# Applicaties.net
KiCad netlist of a schematic drawn in Altium Designer
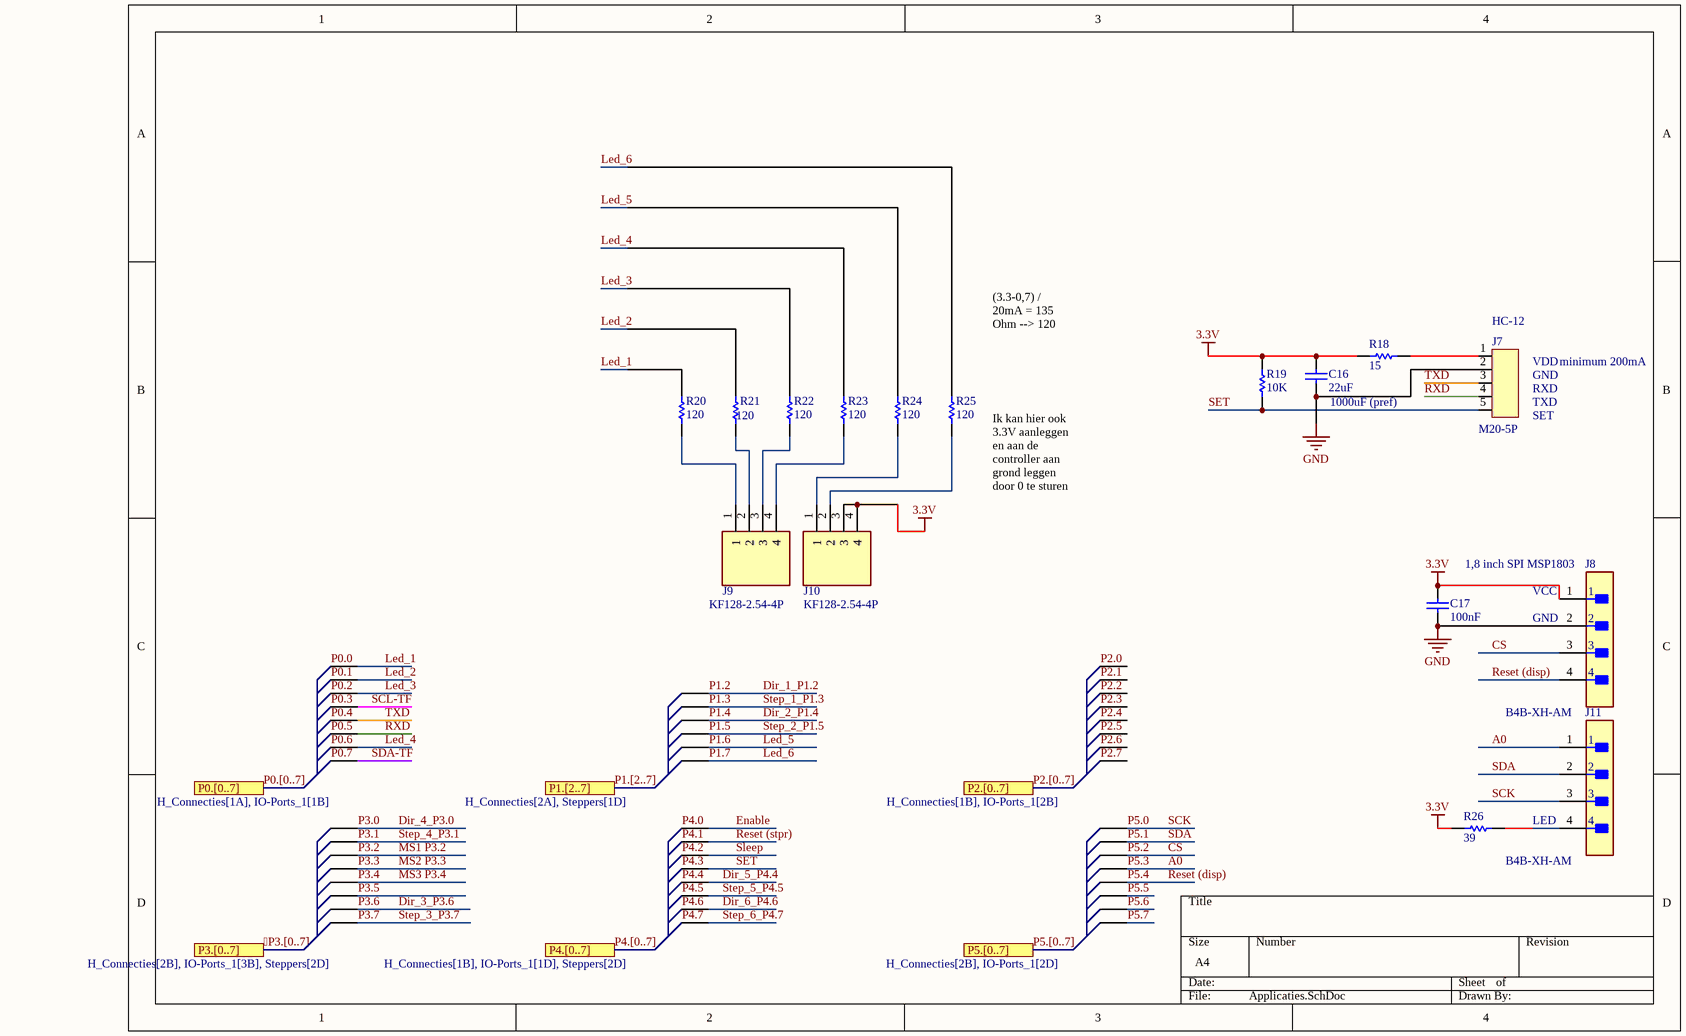
[diagram p0: Applicaties.SchDoc]

(export (version "E")
  (design (tool "Eeschema 10.0.6"))
  (components
    (comp (ref "C16")
      (value "22uF")
      (footprint "CAPC1608X90X35LL15T15")
      (fields
        (field (name "MANUFACTURER") "AVX Interconnect / Elco")
        (field (name "PART NUMBER") "0603ZC101KAT2A")
      )
      (libsource (lib "Altium Content Vault") (part "CAP"))
    )
    (comp (ref "C17")
      (value "100nF")
      (footprint "CAPC1608X90X35LL15T15")
      (fields
        (field (name "MANUFACTURER") "AVX Interconnect / Elco")
        (field (name "PART NUMBER") "0603ZC101KAT2A")
      )
      (libsource (lib "Altium Content Vault") (part "CAP"))
    )
    (comp (ref "J7")
      (value "M20-5P")
      (footprint "M20-5PIN")
      (libsource (lib "Eigen_schemas") (part "M20-5P"))
    )
    (comp (ref "J8")
      (value "B4B-XH-AM")
      (footprint "FP-B4B-XH-A_LF_SN-MFG")
      (description "CONN HEADER VERT 4POS 2.5MM")
      (libsource (lib "Altium Content Vault") (part "299a8cea1bdcbc3624fe62c390fa72c"))
    )
    (comp (ref "J9")
      (value "KF128-2.54-4P")
      (footprint "KF128-2.54-4P")
      (description "Connector")
      (libsource (lib "*") (part "KF128-2.54-4P"))
    )
    (comp (ref "J10")
      (value "KF128-2.54-4P")
      (footprint "KF128-2.54-4P")
      (description "Connector")
      (libsource (lib "*") (part "KF128-2.54-4P"))
    )
    (comp (ref "J11")
      (value "B4B-XH-AM")
      (footprint "FP-B4B-XH-A_LF_SN-MFG")
      (description "CONN HEADER VERT 4POS 2.5MM")
      (libsource (lib "Altium Content Vault") (part "299a8cea1bdcbc3624fe62c390fa72c"))
    )
    (comp (ref "R18")
      (value "15")
      (footprint "RESC1608X55X25LL10T15")
      (fields (field (name "PART NUMBER") "RC0603FR-102KL") (field (name "MANUFACTURER") "Yageo"))
      (libsource (lib "Altium Content Vault") (part "RES"))
    )
    (comp (ref "R19")
      (value "10K")
      (footprint "RESC1608X55X25LL10T15")
      (fields (field (name "PART NUMBER") "RC0603FR-102KL") (field (name "MANUFACTURER") "Yageo"))
      (libsource (lib "Altium Content Vault") (part "RES"))
    )
    (comp (ref "R20")
      (value "120")
      (footprint "RESC1608X55X25LL10T15")
      (fields (field (name "PART NUMBER") "RC0603FR-102KL") (field (name "MANUFACTURER") "Yageo"))
      (libsource (lib "Altium Content Vault") (part "RES"))
    )
    (comp (ref "R21")
      (value "120")
      (footprint "RESC1608X55X25LL10T15")
      (fields (field (name "PART NUMBER") "RC0603FR-102KL") (field (name "MANUFACTURER") "Yageo"))
      (libsource (lib "Altium Content Vault") (part "RES"))
    )
    (comp (ref "R22")
      (value "120")
      (footprint "RESC1608X55X25LL10T15")
      (fields (field (name "PART NUMBER") "RC0603FR-102KL") (field (name "MANUFACTURER") "Yageo"))
      (libsource (lib "Altium Content Vault") (part "RES"))
    )
    (comp (ref "R23")
      (value "120")
      (footprint "RESC1608X55X25LL10T15")
      (fields (field (name "PART NUMBER") "RC0603FR-102KL") (field (name "MANUFACTURER") "Yageo"))
      (libsource (lib "Altium Content Vault") (part "RES"))
    )
    (comp (ref "R24")
      (value "120")
      (footprint "RESC1608X55X25LL10T15")
      (fields (field (name "PART NUMBER") "RC0603FR-102KL") (field (name "MANUFACTURER") "Yageo"))
      (libsource (lib "Altium Content Vault") (part "RES"))
    )
    (comp (ref "R25")
      (value "120")
      (footprint "RESC1608X55X25LL10T15")
      (fields (field (name "PART NUMBER") "RC0603FR-102KL") (field (name "MANUFACTURER") "Yageo"))
      (libsource (lib "Altium Content Vault") (part "RES"))
    )
    (comp (ref "R26")
      (value "39")
      (footprint "RESC1608X55X25LL10T15")
      (fields (field (name "PART NUMBER") "RC0603FR-102KL") (field (name "MANUFACTURER") "Yageo"))
      (libsource (lib "Altium Content Vault") (part "RES"))
    )
  )
  (nets
    (net (code "18") (name "/P0.0") (class "Default")
      (node (ref "R20") (pin "1") (pinfunction "1_1") (pintype "passive"))
    )
    (net (code "19") (name "/P0.1") (class "Default")
      (node (ref "R21") (pin "1") (pinfunction "1_1") (pintype "passive"))
    )
    (net (code "20") (name "/P0.2") (class "Default")
      (node (ref "R22") (pin "1") (pinfunction "1_1") (pintype "passive"))
    )
    (net (code "22") (name "/P0.4") (class "Default")
      (node (ref "J7") (pin "3") (pinfunction "3_3") (pintype "passive"))
    )
    (net (code "23") (name "/P0.5") (class "Default")
      (node (ref "J7") (pin "4") (pinfunction "4_4") (pintype "passive"))
    )
    (net (code "24") (name "/P0.6") (class "Default")
      (node (ref "R23") (pin "1") (pinfunction "1_1") (pintype "passive"))
    )
    (net (code "31") (name "/P1.6") (class "Default")
      (node (ref "R24") (pin "1") (pinfunction "1_1") (pintype "passive"))
    )
    (net (code "32") (name "/P1.7") (class "Default")
      (node (ref "R25") (pin "1") (pinfunction "1_1") (pintype "passive"))
    )
    (net (code "46") (name "/P4.3") (class "Default")
      (node (ref "J7") (pin "5") (pinfunction "5_5") (pintype "passive"))
      (node (ref "R19") (pin "2") (pinfunction "2_2") (pintype "passive"))
    )
    (net (code "52") (name "/P5.0") (class "Default")
      (node (ref "J11") (pin "3") (pinfunction "3_3") (pintype "passive"))
    )
    (net (code "53") (name "/P5.1") (class "Default")
      (node (ref "J11") (pin "2") (pinfunction "2_2") (pintype "passive"))
    )
    (net (code "54") (name "/P5.2") (class "Default")
      (node (ref "J8") (pin "3") (pinfunction "3_3") (pintype "passive"))
    )
    (net (code "55") (name "/P5.3") (class "Default")
      (node (ref "J11") (pin "1") (pinfunction "1_1") (pintype "passive"))
    )
    (net (code "56") (name "/P5.4") (class "Default")
      (node (ref "J8") (pin "4") (pinfunction "4_4") (pintype "passive"))
    )
    (net (code "61") (name "3.3V") (class "Default")
      (node (ref "C16") (pin "2") (pinfunction "2_2") (pintype "passive"))
      (node (ref "C17") (pin "2") (pinfunction "2_2") (pintype "passive"))
      (node (ref "J10") (pin "3") (pinfunction "3_3") (pintype "passive"))
      (node (ref "J10") (pin "4") (pinfunction "4_4") (pintype "passive"))
      (node (ref "J8") (pin "1") (pinfunction "1_1") (pintype "passive"))
      (node (ref "R18") (pin "2") (pinfunction "2_2") (pintype "passive"))
      (node (ref "R19") (pin "1") (pinfunction "1_1") (pintype "passive"))
      (node (ref "R26") (pin "1") (pinfunction "1_1") (pintype "passive"))
    )
    (net (code "62") (name "GND") (class "Default")
      (node (ref "C16") (pin "1") (pinfunction "1_1") (pintype "passive"))
      (node (ref "C17") (pin "1") (pinfunction "1_1") (pintype "passive"))
      (node (ref "J7") (pin "2") (pinfunction "2_2") (pintype "passive"))
      (node (ref "J8") (pin "2") (pinfunction "2_2") (pintype "passive"))
    )
    (net (code "63") (name "Net-(J7-Pad1)") (class "Default")
      (node (ref "J7") (pin "1") (pinfunction "1_1") (pintype "passive"))
      (node (ref "R18") (pin "1") (pinfunction "1_1") (pintype "passive"))
    )
    (net (code "64") (name "Net-(J9-Pad1)") (class "Default")
      (node (ref "J9") (pin "1") (pinfunction "1_1") (pintype "passive"))
      (node (ref "R20") (pin "2") (pinfunction "2_2") (pintype "passive"))
    )
    (net (code "65") (name "Net-(J9-Pad2)") (class "Default")
      (node (ref "J9") (pin "2") (pinfunction "2_2") (pintype "passive"))
      (node (ref "R21") (pin "2") (pinfunction "2_2") (pintype "passive"))
    )
    (net (code "66") (name "Net-(J9-Pad3)") (class "Default")
      (node (ref "J9") (pin "3") (pinfunction "3_3") (pintype "passive"))
      (node (ref "R22") (pin "2") (pinfunction "2_2") (pintype "passive"))
    )
    (net (code "67") (name "Net-(J9-Pad4)") (class "Default")
      (node (ref "J9") (pin "4") (pinfunction "4_4") (pintype "passive"))
      (node (ref "R23") (pin "2") (pinfunction "2_2") (pintype "passive"))
    )
    (net (code "68") (name "Net-(J10-Pad1)") (class "Default")
      (node (ref "J10") (pin "1") (pinfunction "1_1") (pintype "passive"))
      (node (ref "R24") (pin "2") (pinfunction "2_2") (pintype "passive"))
    )
    (net (code "69") (name "Net-(J10-Pad2)") (class "Default")
      (node (ref "J10") (pin "2") (pinfunction "2_2") (pintype "passive"))
      (node (ref "R25") (pin "2") (pinfunction "2_2") (pintype "passive"))
    )
    (net (code "70") (name "Net-(J11-Pad4)") (class "Default")
      (node (ref "J11") (pin "4") (pinfunction "4_4") (pintype "passive"))
      (node (ref "R26") (pin "2") (pinfunction "2_2") (pintype "passive"))
    )
  )
)
